# QRD1114_lista.net
KiCad netlist of a schematic drawn in EAGLE
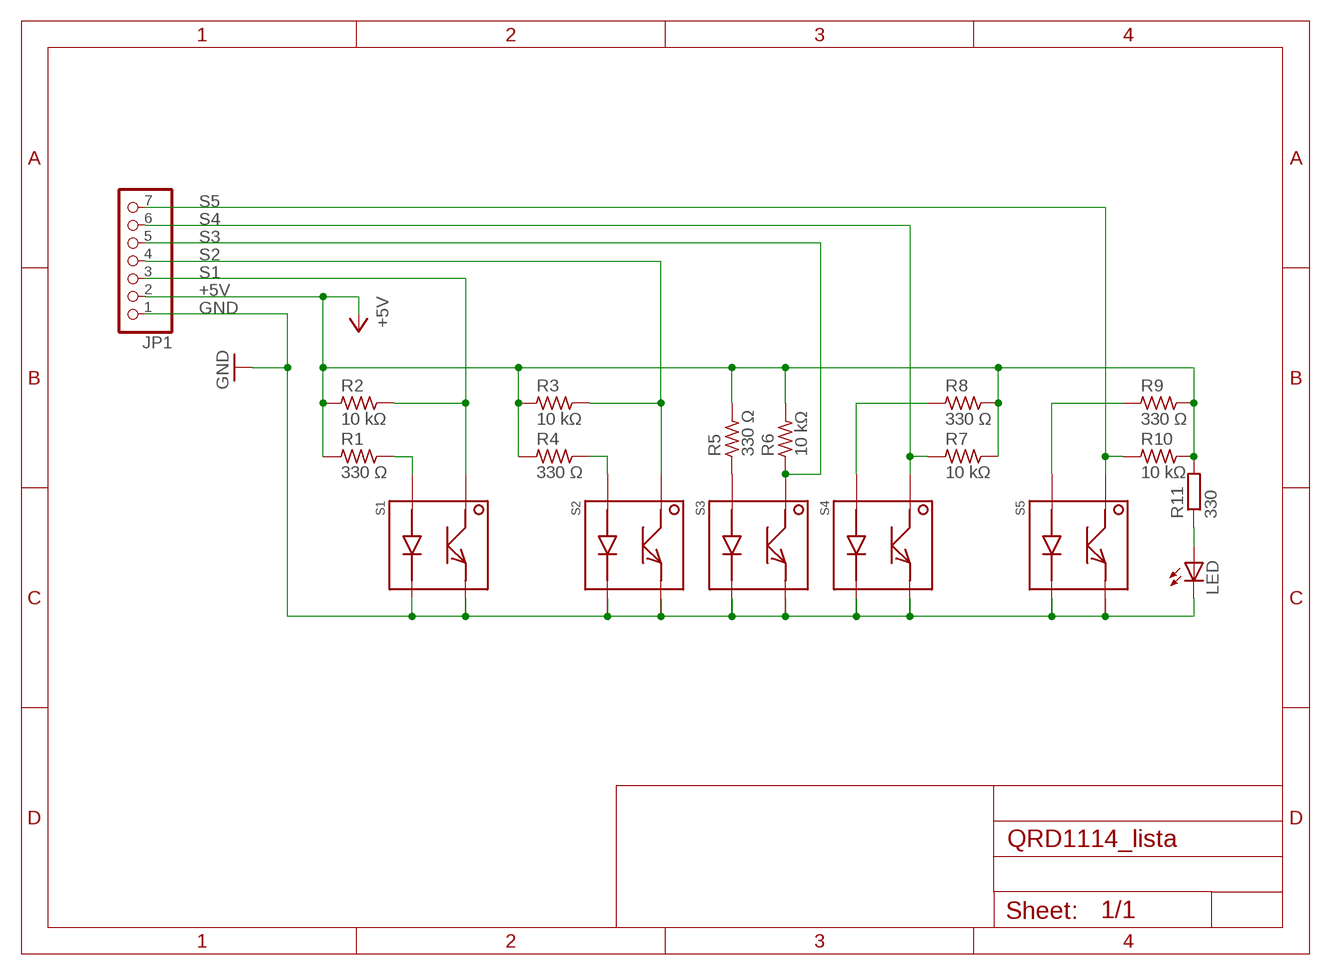
[diagram p0: schematic, sheet 1]

(export (version "E")
  (design (tool "Eeschema 10.0.6"))
  (components
    (comp (ref "JP1")
      (value "PINHD-1X7")
      (footprint "eagle-import:1X07")
      (libsource (lib "eagle-import") (part "PINHD-1X7"))
    )
    (comp (ref "LED")
      (value "LEDCHIPLED-0603-TTW")
      (footprint "eagle-import:CHIPLED-0603-TTW")
      (libsource (lib "eagle-import") (part "LEDCHIPLED-0603-TTW"))
    )
    (comp (ref "R1")
      (value "330 Ω")
      (footprint "eagle-import:R0603")
      (fields (field (name "MF") "VISHAY") (field (name "MPN") "CRCW0805330RFKEA"))
      (libsource (lib "eagle-import") (part "R_0603"))
    )
    (comp (ref "R2")
      (value "10 kΩ")
      (footprint "eagle-import:R0603")
      (libsource (lib "eagle-import") (part "R_0603"))
    )
    (comp (ref "R3")
      (value "10 kΩ")
      (footprint "eagle-import:R0603")
      (libsource (lib "eagle-import") (part "R_0603"))
    )
    (comp (ref "R4")
      (value "330 Ω")
      (footprint "eagle-import:R0603")
      (fields (field (name "MF") "VISHAY") (field (name "MPN") "CRCW0805330RFKEA"))
      (libsource (lib "eagle-import") (part "R_0603"))
    )
    (comp (ref "R5")
      (value "330 Ω")
      (footprint "eagle-import:R0603")
      (fields (field (name "MF") "VISHAY") (field (name "MPN") "CRCW0805330RFKEA"))
      (libsource (lib "eagle-import") (part "R_0603"))
    )
    (comp (ref "R6")
      (value "10 kΩ")
      (footprint "eagle-import:R0603")
      (libsource (lib "eagle-import") (part "R_0603"))
    )
    (comp (ref "R7")
      (value "10 kΩ")
      (footprint "eagle-import:R0603")
      (libsource (lib "eagle-import") (part "R_0603"))
    )
    (comp (ref "R8")
      (value "330 Ω")
      (footprint "eagle-import:R0603")
      (fields (field (name "MF") "VISHAY") (field (name "MPN") "CRCW0805330RFKEA"))
      (libsource (lib "eagle-import") (part "R_0603"))
    )
    (comp (ref "R9")
      (value "330 Ω")
      (footprint "eagle-import:R0603")
      (fields (field (name "MF") "VISHAY") (field (name "MPN") "CRCW0805330RFKEA"))
      (libsource (lib "eagle-import") (part "R_0603"))
    )
    (comp (ref "R10")
      (value "10 kΩ")
      (footprint "eagle-import:R0603")
      (libsource (lib "eagle-import") (part "R_0603"))
    )
    (comp (ref "R11")
      (value "330")
      (footprint "eagle-import:R0805")
      (libsource (lib "eagle-import") (part "R-EU_R0805"))
    )
    (comp (ref "S1")
      (value "QRD1114")
      (footprint "eagle-import:QRD1114")
      (fields (field (name "MF") "ON Semiconductor") (field (name "MF_1") "ON SEMICONDUCTOR"))
      (libsource (lib "eagle-import") (part "QRD1114"))
    )
    (comp (ref "S2")
      (value "QRD1114")
      (footprint "eagle-import:QRD1114")
      (fields (field (name "MF") "ON Semiconductor") (field (name "MF_1") "ON SEMICONDUCTOR"))
      (libsource (lib "eagle-import") (part "QRD1114"))
    )
    (comp (ref "S3")
      (value "QRD1114")
      (footprint "eagle-import:QRD1114")
      (fields (field (name "MF") "ON Semiconductor") (field (name "MF_1") "ON SEMICONDUCTOR"))
      (libsource (lib "eagle-import") (part "QRD1114"))
    )
    (comp (ref "S4")
      (value "QRD1114")
      (footprint "eagle-import:QRD1114")
      (fields (field (name "MF") "ON Semiconductor") (field (name "MF_1") "ON SEMICONDUCTOR"))
      (libsource (lib "eagle-import") (part "QRD1114"))
    )
    (comp (ref "S5")
      (value "QRD1114")
      (footprint "eagle-import:QRD1114")
      (fields (field (name "MF") "ON Semiconductor"))
      (libsource (lib "eagle-import") (part "QRD1114"))
    )
  )
  (nets
    (net (code "1") (name "+5V") (class "Default")
      (node (ref "JP1") (pin "2") (pinfunction "2_2") (pintype "passive"))
      (node (ref "R1") (pin "1") (pinfunction "1_1") (pintype "passive"))
      (node (ref "R10") (pin "2") (pinfunction "2_2") (pintype "passive"))
      (node (ref "R11") (pin "2") (pinfunction "2_2") (pintype "passive"))
      (node (ref "R2") (pin "1") (pinfunction "1_1") (pintype "passive"))
      (node (ref "R3") (pin "1") (pinfunction "1_1") (pintype "passive"))
      (node (ref "R4") (pin "1") (pinfunction "1_1") (pintype "passive"))
      (node (ref "R5") (pin "2") (pinfunction "2_2") (pintype "passive"))
      (node (ref "R6") (pin "2") (pinfunction "2_2") (pintype "passive"))
      (node (ref "R7") (pin "2") (pinfunction "2_2") (pintype "passive"))
      (node (ref "R8") (pin "2") (pinfunction "2_2") (pintype "passive"))
      (node (ref "R9") (pin "2") (pinfunction "2_2") (pintype "passive"))
    )
    (net (code "2") (name "/S1") (class "Default")
      (node (ref "JP1") (pin "3") (pinfunction "3_3") (pintype "passive"))
      (node (ref "R2") (pin "2") (pinfunction "2_2") (pintype "passive"))
      (node (ref "S1") (pin "P$1") (pinfunction "P$1_P$1") (pintype "bidirectional"))
    )
    (net (code "3") (name "/S2") (class "Default")
      (node (ref "JP1") (pin "4") (pinfunction "4_4") (pintype "passive"))
      (node (ref "R3") (pin "2") (pinfunction "2_2") (pintype "passive"))
      (node (ref "S2") (pin "P$1") (pinfunction "P$1_P$1") (pintype "bidirectional"))
    )
    (net (code "4") (name "/S3") (class "Default")
      (node (ref "JP1") (pin "5") (pinfunction "5_5") (pintype "passive"))
      (node (ref "R6") (pin "1") (pinfunction "1_1") (pintype "passive"))
      (node (ref "S3") (pin "P$1") (pinfunction "P$1_P$1") (pintype "bidirectional"))
    )
    (net (code "5") (name "/S4") (class "Default")
      (node (ref "JP1") (pin "6") (pinfunction "6_6") (pintype "passive"))
      (node (ref "R7") (pin "1") (pinfunction "1_1") (pintype "passive"))
      (node (ref "S4") (pin "P$1") (pinfunction "P$1_P$1") (pintype "bidirectional"))
    )
    (net (code "6") (name "/S5") (class "Default")
      (node (ref "JP1") (pin "7") (pinfunction "7_7") (pintype "passive"))
      (node (ref "R10") (pin "1") (pinfunction "1_1") (pintype "passive"))
      (node (ref "S5") (pin "P$1") (pinfunction "P$1_P$1") (pintype "bidirectional"))
    )
    (net (code "7") (name "GND") (class "Default")
      (node (ref "JP1") (pin "1") (pinfunction "1_1") (pintype "passive"))
      (node (ref "LED") (pin "C@1") (pinfunction "C_C@1") (pintype "passive"))
      (node (ref "S1") (pin "P$2") (pinfunction "P$2_P$2") (pintype "bidirectional"))
      (node (ref "S1") (pin "P$4") (pinfunction "P$4_P$4") (pintype "bidirectional"))
      (node (ref "S2") (pin "P$2") (pinfunction "P$2_P$2") (pintype "bidirectional"))
      (node (ref "S2") (pin "P$4") (pinfunction "P$4_P$4") (pintype "bidirectional"))
      (node (ref "S3") (pin "P$2") (pinfunction "P$2_P$2") (pintype "bidirectional"))
      (node (ref "S3") (pin "P$4") (pinfunction "P$4_P$4") (pintype "bidirectional"))
      (node (ref "S4") (pin "P$2") (pinfunction "P$2_P$2") (pintype "bidirectional"))
      (node (ref "S4") (pin "P$4") (pinfunction "P$4_P$4") (pintype "bidirectional"))
      (node (ref "S5") (pin "P$2") (pinfunction "P$2_P$2") (pintype "bidirectional"))
      (node (ref "S5") (pin "P$4") (pinfunction "P$4_P$4") (pintype "bidirectional"))
    )
    (net (code "8") (name "Net-(LED-A)") (class "Default")
      (node (ref "LED") (pin "A@1") (pinfunction "A_A@1") (pintype "passive"))
      (node (ref "R11") (pin "1") (pinfunction "1_1") (pintype "passive"))
    )
    (net (code "9") (name "Net-(R1-Pad2)") (class "Default")
      (node (ref "R1") (pin "2") (pinfunction "2_2") (pintype "passive"))
      (node (ref "S1") (pin "P$3") (pinfunction "P$3_P$3") (pintype "bidirectional"))
    )
    (net (code "10") (name "Net-(R4-Pad2)") (class "Default")
      (node (ref "R4") (pin "2") (pinfunction "2_2") (pintype "passive"))
      (node (ref "S2") (pin "P$3") (pinfunction "P$3_P$3") (pintype "bidirectional"))
    )
    (net (code "11") (name "Net-(R5-Pad1)") (class "Default")
      (node (ref "R5") (pin "1") (pinfunction "1_1") (pintype "passive"))
      (node (ref "S3") (pin "P$3") (pinfunction "P$3_P$3") (pintype "bidirectional"))
    )
    (net (code "12") (name "Net-(R8-Pad1)") (class "Default")
      (node (ref "R8") (pin "1") (pinfunction "1_1") (pintype "passive"))
      (node (ref "S4") (pin "P$3") (pinfunction "P$3_P$3") (pintype "bidirectional"))
    )
    (net (code "13") (name "Net-(R9-Pad1)") (class "Default")
      (node (ref "R9") (pin "1") (pinfunction "1_1") (pintype "passive"))
      (node (ref "S5") (pin "P$3") (pinfunction "P$3_P$3") (pintype "bidirectional"))
    )
  )
)
